# touchpad.net
KiCad netlist of a schematic drawn in Altium Designer
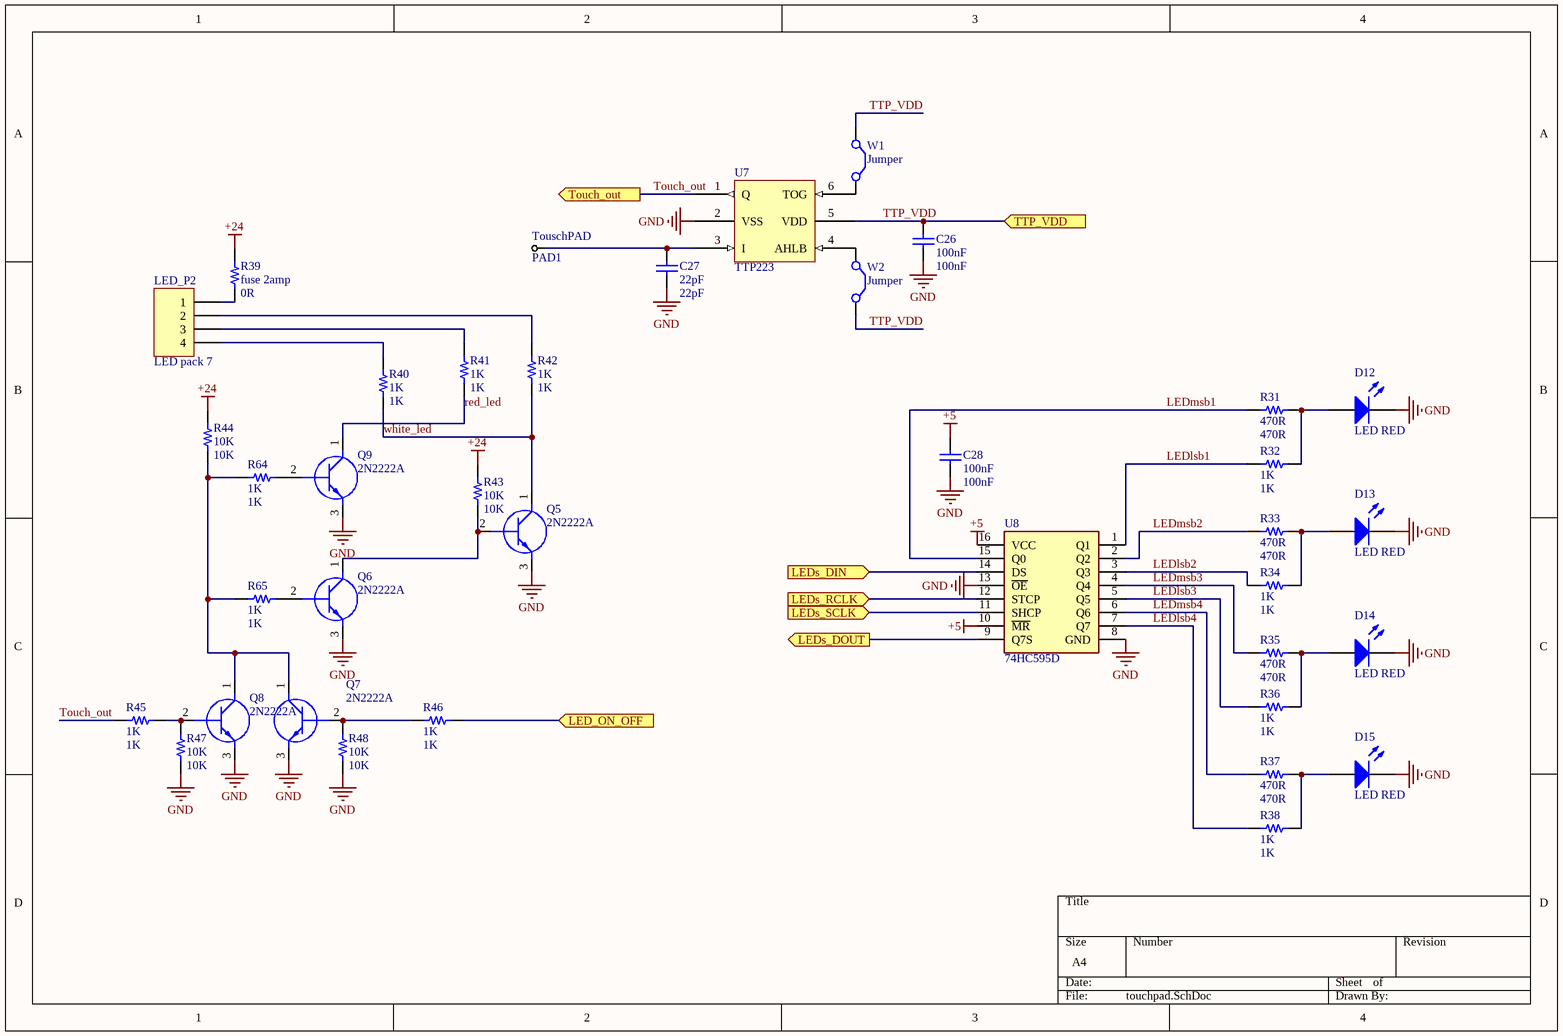
[diagram p0: touchpad.SchDoc]

(export (version "E")
  (design (tool "Eeschema 10.0.6"))
  (components
    (comp (ref "C26")
      (value "100nF")
      (footprint "0603C")
      (description "CAP SMD 0603")
      (fields (field (name "ALTIUM_VALUE") "100nF") (field (name "PUBLISHER") "Altium Limited"))
      (libsource (lib "Miscellaneous Devices") (part "Cap"))
    )
    (comp (ref "C27")
      (value "22pF")
      (footprint "0603C")
      (description "X7R_NPO")
      (fields (field (name "ALTIUM_VALUE") "22pF") (field (name "PUBLISHER") "Altium Limited"))
      (libsource (lib "Miscellaneous Devices") (part "Cap"))
    )
    (comp (ref "C28")
      (value "100nF")
      (footprint "0603C")
      (description "CAP SMD 0603")
      (fields (field (name "ALTIUM_VALUE") "100nF") (field (name "PUBLISHER") "Altium Limited"))
      (libsource (lib "Miscellaneous Devices") (part "Cap"))
    )
    (comp (ref "D12")
      (value "LED RED")
      (footprint "LED_0805 G")
      (description "LED SMD 0805 RED")
      (fields (field (name "PUBLISHER") "Altium Limited"))
      (libsource (lib "Miscellaneous Devices") (part "LED0"))
    )
    (comp (ref "D13")
      (value "LED RED")
      (footprint "LED_0805 G")
      (description "LED SMD 0805 RED")
      (fields (field (name "PUBLISHER") "Altium Limited"))
      (libsource (lib "Miscellaneous Devices") (part "LED0"))
    )
    (comp (ref "D14")
      (value "LED RED")
      (footprint "LED_0805 G")
      (description "LED SMD 0805 RED")
      (fields (field (name "PUBLISHER") "Altium Limited"))
      (libsource (lib "Miscellaneous Devices") (part "LED0"))
    )
    (comp (ref "D15")
      (value "LED RED")
      (footprint "LED_0805 G")
      (description "LED SMD 0805 RED")
      (fields (field (name "PUBLISHER") "Altium Limited"))
      (libsource (lib "Miscellaneous Devices") (part "LED0"))
    )
    (comp (ref "LED_P2")
      (value "LED pack 7")
      (footprint "LED_PAKC_7")
      (description "7led-red white LED pack")
      (fields (field (name "PUBLISHER") "Altium Limited"))
      (libsource (lib "Altium") (part "Header 4"))
    )
    (comp (ref "PAD1")
      (value "TouschPAD")
      (footprint "touchPAD")
      (libsource (lib "Altium (2)") (part "Test Point"))
    )
    (comp (ref "Q5")
      (value "2N2222A")
      (footprint "soT95p280x130-3n")
      (description "Transistor BJT NPN SMD")
      (libsource (lib "*") (part "2N2222A"))
    )
    (comp (ref "Q6")
      (value "2N2222A")
      (footprint "soT95p280x130-3n")
      (description "Transistor BJT NPN SMD")
      (libsource (lib "*") (part "2N2222A"))
    )
    (comp (ref "Q7")
      (value "2N2222A")
      (footprint "soT95p280x130-3n")
      (description "Transistor BJT NPN SMD")
      (libsource (lib "*") (part "2N2222A"))
    )
    (comp (ref "Q8")
      (value "2N2222A")
      (footprint "soT95p280x130-3n")
      (description "Transistor BJT NPN SMD")
      (libsource (lib "*") (part "2N2222A"))
    )
    (comp (ref "Q9")
      (value "2N2222A")
      (footprint "soT95p280x130-3n")
      (description "Transistor BJT NPN SMD")
      (libsource (lib "*") (part "2N2222A"))
    )
    (comp (ref "R31")
      (value "470R")
      (footprint "0603R")
      (description "RES SMD 0603")
      (fields (field (name "PART NUMBER") "RCS0805100KFKEA") (field (name "ALTIUM_VALUE") "470R"))
      (libsource (lib "lamp control-ver2") (part "Resistor"))
    )
    (comp (ref "R32")
      (value "1K")
      (footprint "0603R")
      (description "RES SMD 0603")
      (fields (field (name "PART NUMBER") "RCS0805100KFKEA") (field (name "ALTIUM_VALUE") "1K"))
      (libsource (lib "lamp control-ver2") (part "Resistor"))
    )
    (comp (ref "R33")
      (value "470R")
      (footprint "0603R")
      (description "RES SMD 0603")
      (fields (field (name "PART NUMBER") "RCS0805100KFKEA") (field (name "ALTIUM_VALUE") "470R"))
      (libsource (lib "lamp control-ver2") (part "Resistor"))
    )
    (comp (ref "R34")
      (value "1K")
      (footprint "0603R")
      (description "RES SMD 0603")
      (fields (field (name "PART NUMBER") "RCS0805100KFKEA") (field (name "ALTIUM_VALUE") "1K"))
      (libsource (lib "lamp control-ver2") (part "Resistor"))
    )
    (comp (ref "R35")
      (value "470R")
      (footprint "0603R")
      (description "RES SMD 0603")
      (fields (field (name "PART NUMBER") "RCS0805100KFKEA") (field (name "ALTIUM_VALUE") "470R"))
      (libsource (lib "lamp control-ver2") (part "Resistor"))
    )
    (comp (ref "R36")
      (value "1K")
      (footprint "0603R")
      (description "RES SMD 0603")
      (fields (field (name "PART NUMBER") "RCS0805100KFKEA") (field (name "ALTIUM_VALUE") "1K"))
      (libsource (lib "lamp control-ver2") (part "Resistor"))
    )
    (comp (ref "R37")
      (value "470R")
      (footprint "0603R")
      (description "RES SMD 0603")
      (fields (field (name "PART NUMBER") "RCS0805100KFKEA") (field (name "ALTIUM_VALUE") "470R"))
      (libsource (lib "lamp control-ver2") (part "Resistor"))
    )
    (comp (ref "R38")
      (value "1K")
      (footprint "0603R")
      (description "RES SMD 0603")
      (fields (field (name "PART NUMBER") "RCS0805100KFKEA") (field (name "ALTIUM_VALUE") "1K"))
      (libsource (lib "lamp control-ver2") (part "Resistor"))
    )
    (comp (ref "R39")
      (value "fuse 2amp")
      (footprint "1206 FUSE")
      (description "Fuse 1206")
      (fields (field (name "PART NUMBER") "RCS0805100KFKEA") (field (name "ALTIUM_VALUE") "0R"))
      (libsource (lib "lamp control-ver2") (part "Resistor"))
    )
    (comp (ref "R40")
      (value "1K")
      (footprint "RES1812")
      (description "RES SMD 1812")
      (fields (field (name "PART NUMBER") "RCS0805100KFKEA") (field (name "ALTIUM_VALUE") "1K"))
      (libsource (lib "lamp control-ver2") (part "Resistor"))
    )
    (comp (ref "R41")
      (value "1K")
      (footprint "RES1812")
      (description "RES SMD 1812")
      (fields (field (name "PART NUMBER") "RCS0805100KFKEA") (field (name "ALTIUM_VALUE") "1K"))
      (libsource (lib "lamp control-ver2") (part "Resistor"))
    )
    (comp (ref "R42")
      (value "1K")
      (footprint "RES1812")
      (description "RES SMD 1812")
      (fields (field (name "PART NUMBER") "RCS0805100KFKEA") (field (name "ALTIUM_VALUE") "1K"))
      (libsource (lib "lamp control-ver2") (part "Resistor"))
    )
    (comp (ref "R43")
      (value "10K")
      (footprint "0603R")
      (description "RES SMD 0603")
      (fields (field (name "PART NUMBER") "RCS0805100KFKEA") (field (name "ALTIUM_VALUE") "10K"))
      (libsource (lib "lamp control-ver2") (part "Resistor"))
    )
    (comp (ref "R44")
      (value "10K")
      (footprint "0603R")
      (description "RES SMD 0603")
      (fields (field (name "PART NUMBER") "RCS0805100KFKEA") (field (name "ALTIUM_VALUE") "10K"))
      (libsource (lib "lamp control-ver2") (part "Resistor"))
    )
    (comp (ref "R45")
      (value "1K")
      (footprint "0603R")
      (description "RES SMD 0603")
      (fields (field (name "PART NUMBER") "RCS0805100KFKEA") (field (name "ALTIUM_VALUE") "1K"))
      (libsource (lib "lamp control-ver2") (part "Resistor"))
    )
    (comp (ref "R46")
      (value "1K")
      (footprint "0603R")
      (description "RES SMD 0603")
      (fields (field (name "PART NUMBER") "RCS0805100KFKEA") (field (name "ALTIUM_VALUE") "1K"))
      (libsource (lib "lamp control-ver2") (part "Resistor"))
    )
    (comp (ref "R47")
      (value "10K")
      (footprint "0603R")
      (description "RES SMD 0603")
      (fields (field (name "PART NUMBER") "RCS0805100KFKEA") (field (name "ALTIUM_VALUE") "10K"))
      (libsource (lib "lamp control-ver2") (part "Resistor"))
    )
    (comp (ref "R48")
      (value "10K")
      (footprint "0603R")
      (description "RES SMD 0603")
      (fields (field (name "PART NUMBER") "RCS0805100KFKEA") (field (name "ALTIUM_VALUE") "10K"))
      (libsource (lib "lamp control-ver2") (part "Resistor"))
    )
    (comp (ref "R64")
      (value "1K")
      (footprint "0603R")
      (description "RES SMD 0603")
      (fields (field (name "PART NUMBER") "RCS0805100KFKEA") (field (name "ALTIUM_VALUE") "1K"))
      (libsource (lib "lamp control-ver2") (part "Resistor"))
    )
    (comp (ref "R65")
      (value "1K")
      (footprint "0603R")
      (description "RES SMD 0603")
      (fields (field (name "PART NUMBER") "RCS0805100KFKEA") (field (name "ALTIUM_VALUE") "1K"))
      (libsource (lib "lamp control-ver2") (part "Resistor"))
    )
    (comp (ref "U7")
      (value "TTP223")
      (footprint "SOT23-6_L")
      (description "capacitive touch IC")
      (libsource (lib "Schlib1") (part "ttp223b"))
    )
    (comp (ref "U8")
      (value "74HC595D")
      (footprint "SOIC127P600X175-16N")
      (description "74HC595 SMD")
      (libsource (lib "*") (part "74HC595D"))
    )
    (comp (ref "W1")
      (value "Jumper")
      (footprint "JUMPER")
      (description "Jumper Wire")
      (fields (field (name "PUBLISHER") "Altium Limited"))
      (libsource (lib "Miscellaneous Devices") (part "Jumper"))
    )
    (comp (ref "W2")
      (value "Jumper")
      (footprint "JUMPER")
      (description "Jumper Wire")
      (fields (field (name "PUBLISHER") "Altium Limited"))
      (libsource (lib "Miscellaneous Devices") (part "Jumper"))
    )
  )
  (nets
    (net (code "1") (name "+5") (class "Default")
      (node (ref "C28") (pin "2") (pinfunction "2_2") (pintype "passive"))
      (node (ref "U8") (pin "10") (pinfunction "~{MR}_10") (pintype "passive"))
      (node (ref "U8") (pin "16") (pinfunction "VCC_16") (pintype "passive"))
    )
    (net (code "2") (name "+24") (class "Default")
      (node (ref "R39") (pin "1") (pinfunction "1_1") (pintype "passive"))
      (node (ref "R43") (pin "1") (pinfunction "1_1") (pintype "passive"))
      (node (ref "R44") (pin "1") (pinfunction "1_1") (pintype "passive"))
    )
    (net (code "3") (name "/LED_ON_OFF") (class "Default")
      (node (ref "R46") (pin "2") (pinfunction "2_2") (pintype "passive"))
    )
    (net (code "4") (name "/LEDlsb1") (class "Default")
      (node (ref "R32") (pin "2") (pinfunction "2_2") (pintype "passive"))
      (node (ref "U8") (pin "1") (pinfunction "Q1_1") (pintype "passive"))
    )
    (net (code "5") (name "/LEDlsb2") (class "Default")
      (node (ref "R34") (pin "2") (pinfunction "2_2") (pintype "passive"))
      (node (ref "U8") (pin "3") (pinfunction "Q3_3") (pintype "passive"))
    )
    (net (code "6") (name "/LEDlsb3") (class "Default")
      (node (ref "R36") (pin "2") (pinfunction "2_2") (pintype "passive"))
      (node (ref "U8") (pin "5") (pinfunction "Q5_5") (pintype "passive"))
    )
    (net (code "7") (name "/LEDlsb4") (class "Default")
      (node (ref "R38") (pin "2") (pinfunction "2_2") (pintype "passive"))
      (node (ref "U8") (pin "7") (pinfunction "Q7_7") (pintype "passive"))
    )
    (net (code "8") (name "/LEDmsb1") (class "Default")
      (node (ref "R31") (pin "2") (pinfunction "2_2") (pintype "passive"))
      (node (ref "U8") (pin "15") (pinfunction "Q0_15") (pintype "passive"))
    )
    (net (code "9") (name "/LEDmsb2") (class "Default")
      (node (ref "R33") (pin "2") (pinfunction "2_2") (pintype "passive"))
      (node (ref "U8") (pin "2") (pinfunction "Q2_2") (pintype "passive"))
    )
    (net (code "10") (name "/LEDmsb3") (class "Default")
      (node (ref "R35") (pin "2") (pinfunction "2_2") (pintype "passive"))
      (node (ref "U8") (pin "4") (pinfunction "Q4_4") (pintype "passive"))
    )
    (net (code "11") (name "/LEDmsb4") (class "Default")
      (node (ref "R37") (pin "2") (pinfunction "2_2") (pintype "passive"))
      (node (ref "U8") (pin "6") (pinfunction "Q6_6") (pintype "passive"))
    )
    (net (code "12") (name "/LEDs_DIN") (class "Default")
      (node (ref "U8") (pin "14") (pinfunction "DS_14") (pintype "passive"))
    )
    (net (code "13") (name "/LEDs_DOUT") (class "Default")
      (node (ref "U8") (pin "9") (pinfunction "Q7S_9") (pintype "passive"))
    )
    (net (code "14") (name "/LEDs_RCLK") (class "Default")
      (node (ref "U8") (pin "12") (pinfunction "STCP_12") (pintype "passive"))
    )
    (net (code "15") (name "/LEDs_SCLK") (class "Default")
      (node (ref "U8") (pin "11") (pinfunction "SHCP_11") (pintype "passive"))
    )
    (net (code "16") (name "/TTP_VDD") (class "Default")
      (node (ref "C26") (pin "2") (pinfunction "2_2") (pintype "passive"))
      (node (ref "U7") (pin "5") (pinfunction "VDD_5") (pintype "power_in"))
      (node (ref "W1") (pin "1") (pinfunction "C1_1") (pintype "passive"))
      (node (ref "W2") (pin "2") (pinfunction "C2_2") (pintype "passive"))
    )
    (net (code "17") (name "/Touch_out") (class "Default")
      (node (ref "R45") (pin "1") (pinfunction "1_1") (pintype "passive"))
      (node (ref "U7") (pin "1") (pinfunction "Q_1") (pintype "output"))
    )
    (net (code "18") (name "/red_led") (class "Default")
      (node (ref "Q9") (pin "1") (pinfunction "C_1") (pintype "passive"))
      (node (ref "R41") (pin "2") (pinfunction "2_2") (pintype "passive"))
    )
    (net (code "19") (name "/white_led") (class "Default")
      (node (ref "Q5") (pin "1") (pinfunction "C_1") (pintype "passive"))
      (node (ref "R40") (pin "2") (pinfunction "2_2") (pintype "passive"))
      (node (ref "R42") (pin "2") (pinfunction "2_2") (pintype "passive"))
    )
    (net (code "20") (name "GND") (class "Default")
      (node (ref "C26") (pin "1") (pinfunction "1_1") (pintype "passive"))
      (node (ref "C27") (pin "1") (pinfunction "1_1") (pintype "passive"))
      (node (ref "C28") (pin "1") (pinfunction "1_1") (pintype "passive"))
      (node (ref "D12") (pin "2") (pinfunction "K_2") (pintype "passive"))
      (node (ref "D13") (pin "2") (pinfunction "K_2") (pintype "passive"))
      (node (ref "D14") (pin "2") (pinfunction "K_2") (pintype "passive"))
      (node (ref "D15") (pin "2") (pinfunction "K_2") (pintype "passive"))
      (node (ref "Q5") (pin "3") (pinfunction "E_3") (pintype "passive"))
      (node (ref "Q6") (pin "3") (pinfunction "E_3") (pintype "passive"))
      (node (ref "Q7") (pin "3") (pinfunction "E_3") (pintype "passive"))
      (node (ref "Q8") (pin "3") (pinfunction "E_3") (pintype "passive"))
      (node (ref "Q9") (pin "3") (pinfunction "E_3") (pintype "passive"))
      (node (ref "R47") (pin "2") (pinfunction "2_2") (pintype "passive"))
      (node (ref "R48") (pin "2") (pinfunction "2_2") (pintype "passive"))
      (node (ref "U7") (pin "2") (pinfunction "VSS_2") (pintype "power_in"))
      (node (ref "U8") (pin "13") (pinfunction "~{OE}_13") (pintype "passive"))
      (node (ref "U8") (pin "8") (pinfunction "GND_8") (pintype "passive"))
    )
    (net (code "21") (name "Net-(D12-A)") (class "Default")
      (node (ref "D12") (pin "1") (pinfunction "A_1") (pintype "passive"))
      (node (ref "R31") (pin "1") (pinfunction "1_1") (pintype "passive"))
      (node (ref "R32") (pin "1") (pinfunction "1_1") (pintype "passive"))
    )
    (net (code "22") (name "Net-(D13-A)") (class "Default")
      (node (ref "D13") (pin "1") (pinfunction "A_1") (pintype "passive"))
      (node (ref "R33") (pin "1") (pinfunction "1_1") (pintype "passive"))
      (node (ref "R34") (pin "1") (pinfunction "1_1") (pintype "passive"))
    )
    (net (code "23") (name "Net-(D14-A)") (class "Default")
      (node (ref "D14") (pin "1") (pinfunction "A_1") (pintype "passive"))
      (node (ref "R35") (pin "1") (pinfunction "1_1") (pintype "passive"))
      (node (ref "R36") (pin "1") (pinfunction "1_1") (pintype "passive"))
    )
    (net (code "24") (name "Net-(D15-A)") (class "Default")
      (node (ref "D15") (pin "1") (pinfunction "A_1") (pintype "passive"))
      (node (ref "R37") (pin "1") (pinfunction "1_1") (pintype "passive"))
      (node (ref "R38") (pin "1") (pinfunction "1_1") (pintype "passive"))
    )
    (net (code "25") (name "Net-(LED_P2-Pad1)") (class "Default")
      (node (ref "LED_P2") (pin "1") (pinfunction "1_1") (pintype "passive"))
      (node (ref "R39") (pin "2") (pinfunction "2_2") (pintype "passive"))
    )
    (net (code "26") (name "Net-(LED_P2-Pad2)") (class "Default")
      (node (ref "LED_P2") (pin "2") (pinfunction "2_2") (pintype "passive"))
      (node (ref "R42") (pin "1") (pinfunction "1_1") (pintype "passive"))
    )
    (net (code "27") (name "Net-(LED_P2-Pad3)") (class "Default")
      (node (ref "LED_P2") (pin "3") (pinfunction "3_3") (pintype "passive"))
      (node (ref "R41") (pin "1") (pinfunction "1_1") (pintype "passive"))
    )
    (net (code "28") (name "Net-(LED_P2-Pad4)") (class "Default")
      (node (ref "LED_P2") (pin "4") (pinfunction "4_4") (pintype "passive"))
      (node (ref "R40") (pin "1") (pinfunction "1_1") (pintype "passive"))
    )
    (net (code "29") (name "Net-(PAD1-T)") (class "Default")
      (node (ref "C27") (pin "2") (pinfunction "2_2") (pintype "passive"))
      (node (ref "PAD1") (pin "1") (pinfunction "T_1") (pintype "passive"))
      (node (ref "U7") (pin "3") (pinfunction "I_3") (pintype "input"))
    )
    (net (code "30") (name "Net-(Q5-B)") (class "Default")
      (node (ref "Q5") (pin "2") (pinfunction "B_2") (pintype "passive"))
      (node (ref "Q6") (pin "1") (pinfunction "C_1") (pintype "passive"))
      (node (ref "R43") (pin "2") (pinfunction "2_2") (pintype "passive"))
    )
    (net (code "31") (name "Net-(Q6-B)") (class "Default")
      (node (ref "Q6") (pin "2") (pinfunction "B_2") (pintype "passive"))
      (node (ref "R65") (pin "2") (pinfunction "2_2") (pintype "passive"))
    )
    (net (code "32") (name "Net-(Q7-B)") (class "Default")
      (node (ref "Q7") (pin "2") (pinfunction "B_2") (pintype "passive"))
      (node (ref "R46") (pin "1") (pinfunction "1_1") (pintype "passive"))
      (node (ref "R48") (pin "1") (pinfunction "1_1") (pintype "passive"))
    )
    (net (code "33") (name "Net-(Q7-C)") (class "Default")
      (node (ref "Q7") (pin "1") (pinfunction "C_1") (pintype "passive"))
      (node (ref "Q8") (pin "1") (pinfunction "C_1") (pintype "passive"))
      (node (ref "R44") (pin "2") (pinfunction "2_2") (pintype "passive"))
      (node (ref "R64") (pin "1") (pinfunction "1_1") (pintype "passive"))
      (node (ref "R65") (pin "1") (pinfunction "1_1") (pintype "passive"))
    )
    (net (code "34") (name "Net-(Q8-B)") (class "Default")
      (node (ref "Q8") (pin "2") (pinfunction "B_2") (pintype "passive"))
      (node (ref "R45") (pin "2") (pinfunction "2_2") (pintype "passive"))
      (node (ref "R47") (pin "1") (pinfunction "1_1") (pintype "passive"))
    )
    (net (code "35") (name "Net-(Q9-B)") (class "Default")
      (node (ref "Q9") (pin "2") (pinfunction "B_2") (pintype "passive"))
      (node (ref "R64") (pin "2") (pinfunction "2_2") (pintype "passive"))
    )
    (net (code "36") (name "Net-(U7-AHLB)") (class "Default")
      (node (ref "U7") (pin "4") (pinfunction "AHLB_4") (pintype "input"))
      (node (ref "W2") (pin "1") (pinfunction "C1_1") (pintype "passive"))
    )
    (net (code "37") (name "Net-(U7-TOG)") (class "Default")
      (node (ref "U7") (pin "6") (pinfunction "TOG_6") (pintype "input"))
      (node (ref "W1") (pin "2") (pinfunction "C2_2") (pintype "passive"))
    )
  )
)
